# ModSynth_PCB.net
KiCad netlist of a schematic drawn in EAGLE
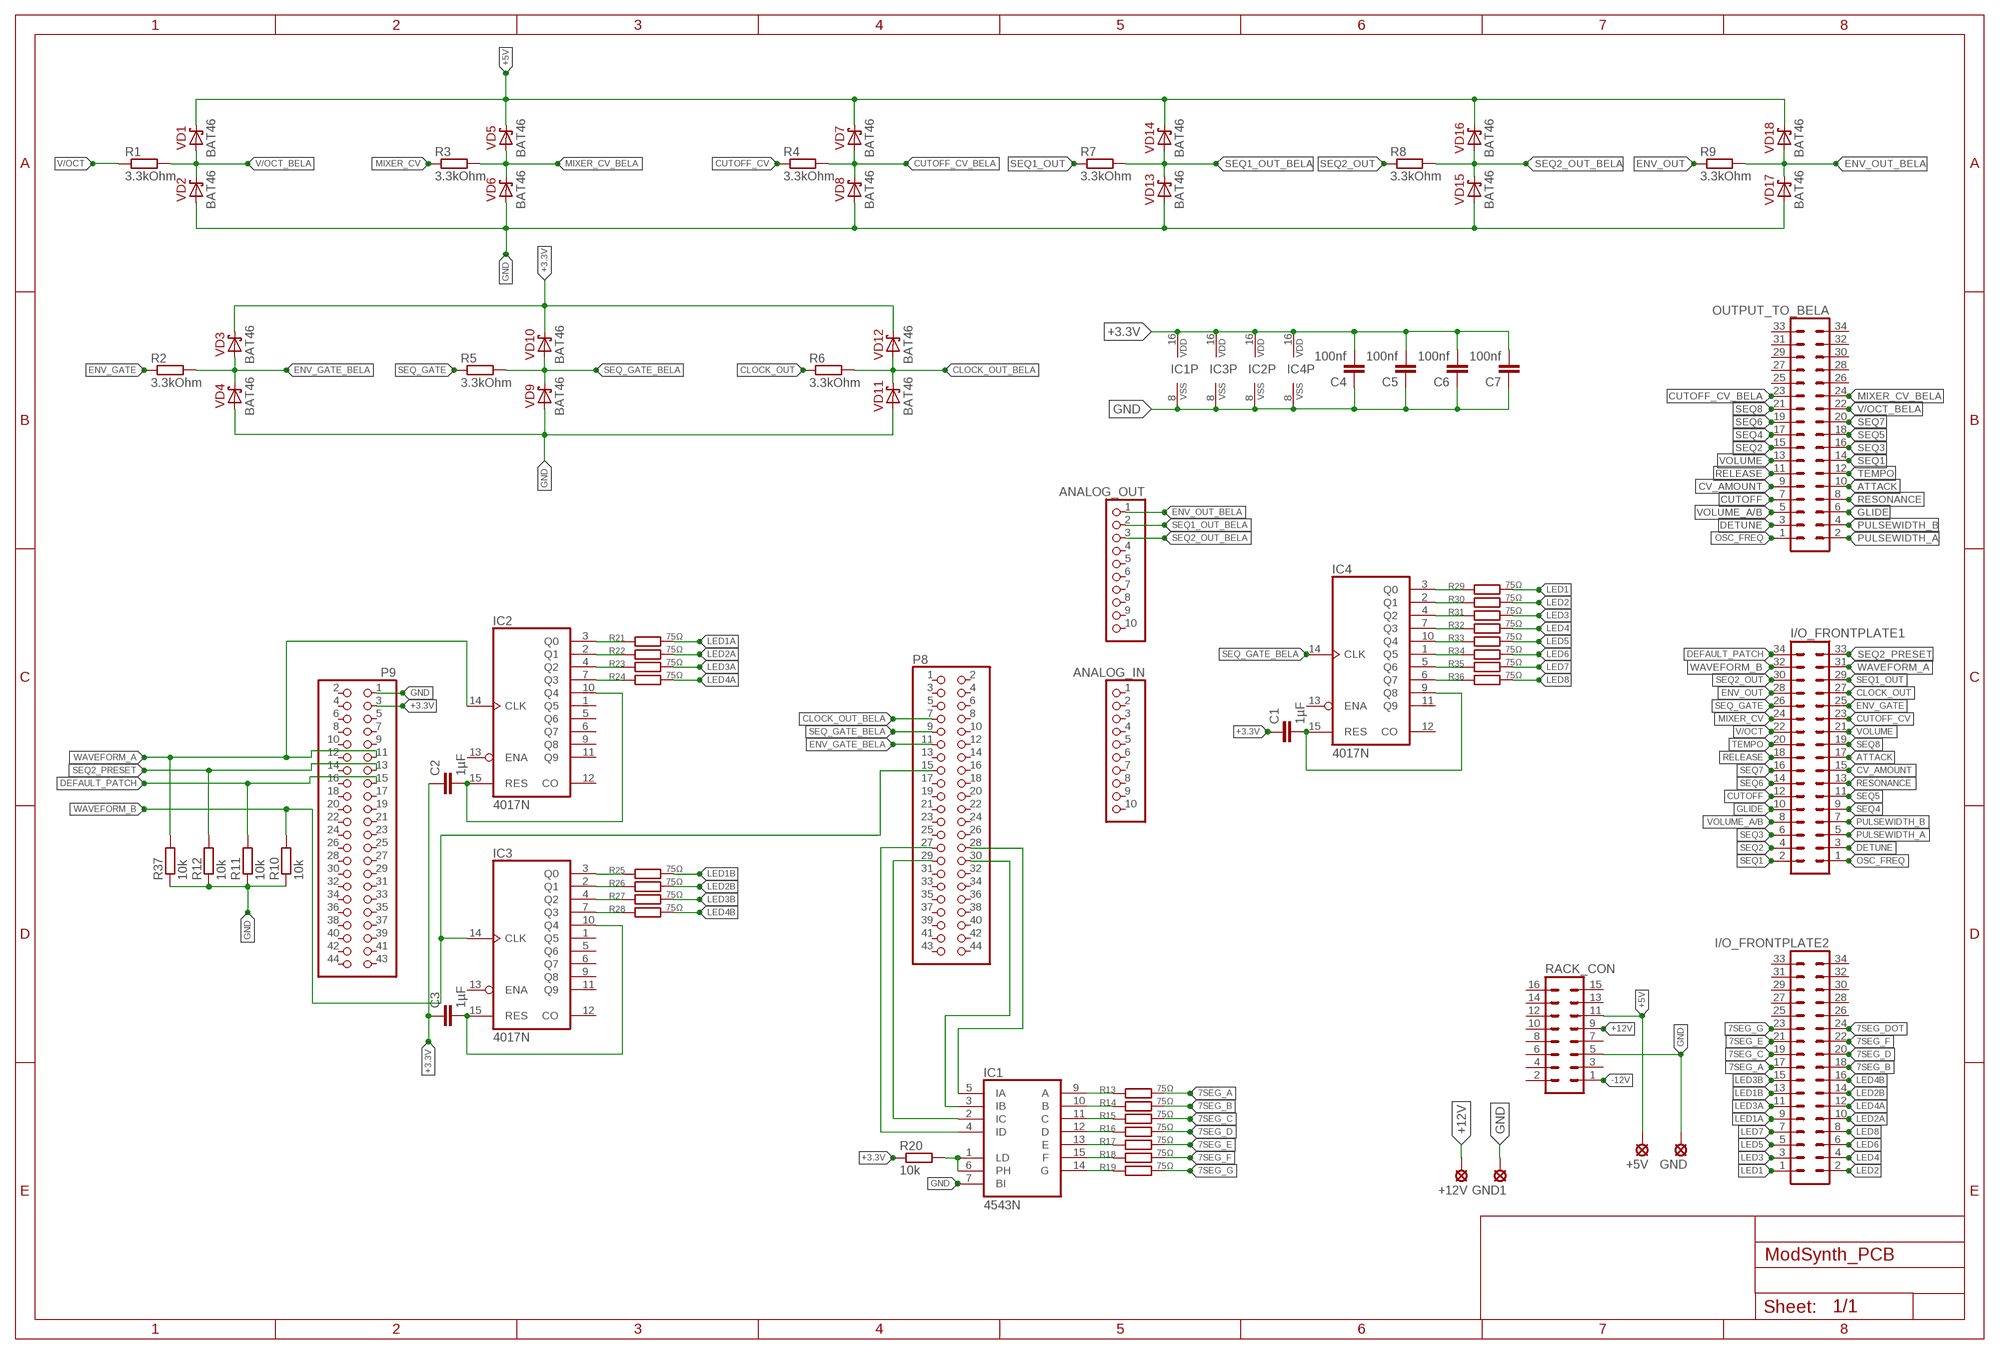
[diagram p0: schematic, sheet 1]

(export (version "E")
  (design (tool "Eeschema 10.0.6"))
  (components
    (comp (ref "+5V")
      (value "LSP10")
      (footprint "eagle-import:LSP10")
      (libsource (lib "eagle-import") (part "LSP10"))
    )
    (comp (ref "+12V")
      (value "LSP10")
      (footprint "eagle-import:LSP10")
      (libsource (lib "eagle-import") (part "LSP10"))
    )
    (comp (ref "ANALOG_IN")
      (value "PINHD-1X10")
      (footprint "eagle-import:1X10")
      (libsource (lib "eagle-import") (part "PINHD-1X10"))
    )
    (comp (ref "ANALOG_OUT")
      (value "PINHD-1X10")
      (footprint "eagle-import:1X10")
      (libsource (lib "eagle-import") (part "PINHD-1X10"))
    )
    (comp (ref "C1")
      (value "1µF")
      (footprint "eagle-import:C025-025X050")
      (libsource (lib "eagle-import") (part "C-EU025-025X050"))
    )
    (comp (ref "C2")
      (value "1µF")
      (footprint "eagle-import:C025-025X050")
      (libsource (lib "eagle-import") (part "C-EU025-025X050"))
    )
    (comp (ref "C3")
      (value "1µF")
      (footprint "eagle-import:C025-025X050")
      (libsource (lib "eagle-import") (part "C-EU025-025X050"))
    )
    (comp (ref "C4")
      (value "100nf")
      (footprint "eagle-import:C025-025X050")
      (libsource (lib "eagle-import") (part "C-EU025-025X050"))
    )
    (comp (ref "C5")
      (value "100nf")
      (footprint "eagle-import:C025-025X050")
      (libsource (lib "eagle-import") (part "C-EU025-025X050"))
    )
    (comp (ref "C6")
      (value "100nf")
      (footprint "eagle-import:C025-025X050")
      (libsource (lib "eagle-import") (part "C-EU025-025X050"))
    )
    (comp (ref "C7")
      (value "100nf")
      (footprint "eagle-import:C025-025X050")
      (libsource (lib "eagle-import") (part "C-EU025-025X050"))
    )
    (comp (ref "GND")
      (value "LSP10")
      (footprint "eagle-import:LSP10")
      (libsource (lib "eagle-import") (part "LSP10"))
    )
    (comp (ref "GND1")
      (value "LSP10")
      (footprint "eagle-import:LSP10")
      (libsource (lib "eagle-import") (part "LSP10"))
    )
    (comp (ref "I/O_FRONTPLATE1")
      (value "ML34")
      (footprint "eagle-import:ML34")
      (libsource (lib "eagle-import") (part "ML34"))
    )
    (comp (ref "I/O_FRONTPLATE2")
      (value "ML34")
      (footprint "eagle-import:ML34")
      (libsource (lib "eagle-import") (part "ML34"))
    )
    (comp (ref "IC1")
      (value "4543N")
      (footprint "eagle-import:DIL16")
      (libsource (lib "eagle-import") (part "4543N"))
    )
    (comp (ref "IC2")
      (value "4017N")
      (footprint "eagle-import:DIL16")
      (libsource (lib "eagle-import") (part "4017N"))
    )
    (comp (ref "IC3")
      (value "4017N")
      (footprint "eagle-import:DIL16")
      (libsource (lib "eagle-import") (part "4017N"))
    )
    (comp (ref "IC4")
      (value "4017N")
      (footprint "eagle-import:DIL16")
      (libsource (lib "eagle-import") (part "4017N"))
    )
    (comp (ref "OUTPUT_TO_BELA")
      (value "ML34")
      (footprint "eagle-import:ML34")
      (libsource (lib "eagle-import") (part "ML34"))
    )
    (comp (ref "P8")
      (value "PINHD-2X22")
      (footprint "eagle-import:2X22")
      (libsource (lib "eagle-import") (part "PINHD-2X22"))
    )
    (comp (ref "P9")
      (value "PINHD-2X22")
      (footprint "eagle-import:2X22")
      (libsource (lib "eagle-import") (part "PINHD-2X22"))
    )
    (comp (ref "R1")
      (value "3.3kOhm")
      (footprint "eagle-import:0204_7")
      (libsource (lib "eagle-import") (part "R-EU_0204/7"))
    )
    (comp (ref "R2")
      (value "3.3kOhm")
      (footprint "eagle-import:0204_7")
      (libsource (lib "eagle-import") (part "R-EU_0204/7"))
    )
    (comp (ref "R3")
      (value "3.3kOhm")
      (footprint "eagle-import:0204_7")
      (libsource (lib "eagle-import") (part "R-EU_0204/7"))
    )
    (comp (ref "R4")
      (value "3.3kOhm")
      (footprint "eagle-import:0204_7")
      (libsource (lib "eagle-import") (part "R-EU_0204/7"))
    )
    (comp (ref "R5")
      (value "3.3kOhm")
      (footprint "eagle-import:0204_7")
      (libsource (lib "eagle-import") (part "R-EU_0204/7"))
    )
    (comp (ref "R6")
      (value "3.3kOhm")
      (footprint "eagle-import:0204_7")
      (libsource (lib "eagle-import") (part "R-EU_0204/7"))
    )
    (comp (ref "R7")
      (value "3.3kOhm")
      (footprint "eagle-import:0204_7")
      (libsource (lib "eagle-import") (part "R-EU_0204/7"))
    )
    (comp (ref "R8")
      (value "3.3kOhm")
      (footprint "eagle-import:0204_7")
      (libsource (lib "eagle-import") (part "R-EU_0204/7"))
    )
    (comp (ref "R9")
      (value "3.3kOhm")
      (footprint "eagle-import:0204_7")
      (libsource (lib "eagle-import") (part "R-EU_0204/7"))
    )
    (comp (ref "R10")
      (value "10k")
      (footprint "eagle-import:0204_7")
      (libsource (lib "eagle-import") (part "R-EU_0204/7"))
    )
    (comp (ref "R11")
      (value "10k")
      (footprint "eagle-import:0204_7")
      (libsource (lib "eagle-import") (part "R-EU_0204/7"))
    )
    (comp (ref "R12")
      (value "10k")
      (footprint "eagle-import:0204_7")
      (libsource (lib "eagle-import") (part "R-EU_0204/7"))
    )
    (comp (ref "R13")
      (value "75Ω")
      (footprint "eagle-import:0204_7")
      (libsource (lib "eagle-import") (part "R-EU_0204/7"))
    )
    (comp (ref "R14")
      (value "75Ω")
      (footprint "eagle-import:0204_7")
      (libsource (lib "eagle-import") (part "R-EU_0204/7"))
    )
    (comp (ref "R15")
      (value "75Ω")
      (footprint "eagle-import:0204_7")
      (libsource (lib "eagle-import") (part "R-EU_0204/7"))
    )
    (comp (ref "R16")
      (value "75Ω")
      (footprint "eagle-import:0204_7")
      (libsource (lib "eagle-import") (part "R-EU_0204/7"))
    )
    (comp (ref "R17")
      (value "75Ω")
      (footprint "eagle-import:0204_7")
      (libsource (lib "eagle-import") (part "R-EU_0204/7"))
    )
    (comp (ref "R18")
      (value "75Ω")
      (footprint "eagle-import:0204_7")
      (libsource (lib "eagle-import") (part "R-EU_0204/7"))
    )
    (comp (ref "R19")
      (value "75Ω")
      (footprint "eagle-import:0204_7")
      (libsource (lib "eagle-import") (part "R-EU_0204/7"))
    )
    (comp (ref "R20")
      (value "10k")
      (footprint "eagle-import:0204_7")
      (libsource (lib "eagle-import") (part "R-EU_0204/7"))
    )
    (comp (ref "R21")
      (value "75Ω")
      (footprint "eagle-import:0204_7")
      (libsource (lib "eagle-import") (part "R-EU_0204/7"))
    )
    (comp (ref "R22")
      (value "75Ω")
      (footprint "eagle-import:0204_7")
      (libsource (lib "eagle-import") (part "R-EU_0204/7"))
    )
    (comp (ref "R23")
      (value "75Ω")
      (footprint "eagle-import:0204_7")
      (libsource (lib "eagle-import") (part "R-EU_0204/7"))
    )
    (comp (ref "R24")
      (value "75Ω")
      (footprint "eagle-import:0204_7")
      (libsource (lib "eagle-import") (part "R-EU_0204/7"))
    )
    (comp (ref "R25")
      (value "75Ω")
      (footprint "eagle-import:0204_7")
      (libsource (lib "eagle-import") (part "R-EU_0204/7"))
    )
    (comp (ref "R26")
      (value "75Ω")
      (footprint "eagle-import:0204_7")
      (libsource (lib "eagle-import") (part "R-EU_0204/7"))
    )
    (comp (ref "R27")
      (value "75Ω")
      (footprint "eagle-import:0204_7")
      (libsource (lib "eagle-import") (part "R-EU_0204/7"))
    )
    (comp (ref "R28")
      (value "75Ω")
      (footprint "eagle-import:0204_7")
      (libsource (lib "eagle-import") (part "R-EU_0204/7"))
    )
    (comp (ref "R29")
      (value "75Ω")
      (footprint "eagle-import:0204_7")
      (libsource (lib "eagle-import") (part "R-EU_0204/7"))
    )
    (comp (ref "R30")
      (value "75Ω")
      (footprint "eagle-import:0204_7")
      (libsource (lib "eagle-import") (part "R-EU_0204/7"))
    )
    (comp (ref "R31")
      (value "75Ω")
      (footprint "eagle-import:0204_7")
      (libsource (lib "eagle-import") (part "R-EU_0204/7"))
    )
    (comp (ref "R32")
      (value "75Ω")
      (footprint "eagle-import:0204_7")
      (libsource (lib "eagle-import") (part "R-EU_0204/7"))
    )
    (comp (ref "R33")
      (value "75Ω")
      (footprint "eagle-import:0204_7")
      (libsource (lib "eagle-import") (part "R-EU_0204/7"))
    )
    (comp (ref "R34")
      (value "75Ω")
      (footprint "eagle-import:0204_7")
      (libsource (lib "eagle-import") (part "R-EU_0204/7"))
    )
    (comp (ref "R35")
      (value "75Ω")
      (footprint "eagle-import:0204_7")
      (libsource (lib "eagle-import") (part "R-EU_0204/7"))
    )
    (comp (ref "R36")
      (value "75Ω")
      (footprint "eagle-import:0204_7")
      (libsource (lib "eagle-import") (part "R-EU_0204/7"))
    )
    (comp (ref "R37")
      (value "10k")
      (footprint "eagle-import:0204_7")
      (libsource (lib "eagle-import") (part "R-EU_0204/7"))
    )
    (comp (ref "RACK_CON")
      (value "ML16")
      (footprint "eagle-import:ML16")
      (libsource (lib "eagle-import") (part "ML16"))
    )
    (comp (ref "VD1")
      (value "BAT46")
      (footprint "eagle-import:DO35-7")
      (libsource (lib "eagle-import") (part "?BAT46"))
    )
    (comp (ref "VD2")
      (value "BAT46")
      (footprint "eagle-import:DO35-7")
      (libsource (lib "eagle-import") (part "?BAT46"))
    )
    (comp (ref "VD3")
      (value "BAT46")
      (footprint "eagle-import:DO35-7")
      (libsource (lib "eagle-import") (part "?BAT46"))
    )
    (comp (ref "VD4")
      (value "BAT46")
      (footprint "eagle-import:DO35-7")
      (libsource (lib "eagle-import") (part "?BAT46"))
    )
    (comp (ref "VD5")
      (value "BAT46")
      (footprint "eagle-import:DO35-7")
      (libsource (lib "eagle-import") (part "?BAT46"))
    )
    (comp (ref "VD6")
      (value "BAT46")
      (footprint "eagle-import:DO35-7")
      (libsource (lib "eagle-import") (part "?BAT46"))
    )
    (comp (ref "VD7")
      (value "BAT46")
      (footprint "eagle-import:DO35-7")
      (libsource (lib "eagle-import") (part "?BAT46"))
    )
    (comp (ref "VD8")
      (value "BAT46")
      (footprint "eagle-import:DO35-7")
      (libsource (lib "eagle-import") (part "?BAT46"))
    )
    (comp (ref "VD9")
      (value "BAT46")
      (footprint "eagle-import:DO35-7")
      (libsource (lib "eagle-import") (part "?BAT46"))
    )
    (comp (ref "VD10")
      (value "BAT46")
      (footprint "eagle-import:DO35-7")
      (libsource (lib "eagle-import") (part "?BAT46"))
    )
    (comp (ref "VD11")
      (value "BAT46")
      (footprint "eagle-import:DO35-7")
      (libsource (lib "eagle-import") (part "?BAT46"))
    )
    (comp (ref "VD12")
      (value "BAT46")
      (footprint "eagle-import:DO35-7")
      (libsource (lib "eagle-import") (part "?BAT46"))
    )
    (comp (ref "VD13")
      (value "BAT46")
      (footprint "eagle-import:DO35-7")
      (libsource (lib "eagle-import") (part "?BAT46"))
    )
    (comp (ref "VD14")
      (value "BAT46")
      (footprint "eagle-import:DO35-7")
      (libsource (lib "eagle-import") (part "?BAT46"))
    )
    (comp (ref "VD15")
      (value "BAT46")
      (footprint "eagle-import:DO35-7")
      (libsource (lib "eagle-import") (part "?BAT46"))
    )
    (comp (ref "VD16")
      (value "BAT46")
      (footprint "eagle-import:DO35-7")
      (libsource (lib "eagle-import") (part "?BAT46"))
    )
    (comp (ref "VD17")
      (value "BAT46")
      (footprint "eagle-import:DO35-7")
      (libsource (lib "eagle-import") (part "?BAT46"))
    )
    (comp (ref "VD18")
      (value "BAT46")
      (footprint "eagle-import:DO35-7")
      (libsource (lib "eagle-import") (part "?BAT46"))
    )
  )
  (nets
    (net (code "1") (name "+3.3V") (class "Default")
      (node (ref "C1") (pin "1") (pinfunction "1_1") (pintype "passive"))
      (node (ref "C2") (pin "1") (pinfunction "1_1") (pintype "passive"))
      (node (ref "C3") (pin "1") (pinfunction "1_1") (pintype "passive"))
      (node (ref "C4") (pin "2") (pinfunction "2_2") (pintype "passive"))
      (node (ref "C5") (pin "2") (pinfunction "2_2") (pintype "passive"))
      (node (ref "C6") (pin "2") (pinfunction "2_2") (pintype "passive"))
      (node (ref "C7") (pin "2") (pinfunction "2_2") (pintype "passive"))
      (node (ref "IC1") (pin "16") (pinfunction "VDD_16") (pintype "power_in"))
      (node (ref "IC2") (pin "16") (pinfunction "VDD_16") (pintype "power_in"))
      (node (ref "IC3") (pin "16") (pinfunction "VDD_16") (pintype "power_in"))
      (node (ref "IC4") (pin "16") (pinfunction "VDD_16") (pintype "power_in"))
      (node (ref "P9") (pin "3") (pinfunction "3_3") (pintype "passive"))
      (node (ref "R20") (pin "1") (pinfunction "1_1") (pintype "passive"))
      (node (ref "VD10") (pin "C") (pinfunction "C_C") (pintype "passive"))
      (node (ref "VD12") (pin "C") (pinfunction "C_C") (pintype "passive"))
      (node (ref "VD3") (pin "C") (pinfunction "C_C") (pintype "passive"))
    )
    (net (code "2") (name "+5V") (class "Default")
      (node (ref "+5V") (pin "MP") (pinfunction "MP_MP") (pintype "passive"))
      (node (ref "RACK_CON") (pin "11") (pinfunction "11_11") (pintype "passive"))
      (node (ref "VD1") (pin "C") (pinfunction "C_C") (pintype "passive"))
      (node (ref "VD14") (pin "C") (pinfunction "C_C") (pintype "passive"))
      (node (ref "VD16") (pin "C") (pinfunction "C_C") (pintype "passive"))
      (node (ref "VD18") (pin "C") (pinfunction "C_C") (pintype "passive"))
      (node (ref "VD5") (pin "C") (pinfunction "C_C") (pintype "passive"))
      (node (ref "VD7") (pin "C") (pinfunction "C_C") (pintype "passive"))
    )
    (net (code "3") (name "+12V") (class "Default")
      (node (ref "+12V") (pin "MP") (pinfunction "MP_MP") (pintype "passive"))
      (node (ref "RACK_CON") (pin "9") (pinfunction "9_9") (pintype "passive"))
    )
    (net (code "4") (name "-12V") (class "Default")
      (node (ref "RACK_CON") (pin "1") (pinfunction "1_1") (pintype "passive"))
    )
    (net (code "5") (name "7SEG_A") (class "Default")
      (node (ref "I/O_FRONTPLATE2") (pin "17") (pinfunction "17_17") (pintype "passive"))
      (node (ref "R13") (pin "2") (pinfunction "2_2") (pintype "passive"))
    )
    (net (code "6") (name "7SEG_B") (class "Default")
      (node (ref "I/O_FRONTPLATE2") (pin "18") (pinfunction "18_18") (pintype "passive"))
      (node (ref "R14") (pin "2") (pinfunction "2_2") (pintype "passive"))
    )
    (net (code "7") (name "7SEG_C") (class "Default")
      (node (ref "I/O_FRONTPLATE2") (pin "19") (pinfunction "19_19") (pintype "passive"))
      (node (ref "R15") (pin "2") (pinfunction "2_2") (pintype "passive"))
    )
    (net (code "8") (name "7SEG_D") (class "Default")
      (node (ref "I/O_FRONTPLATE2") (pin "20") (pinfunction "20_20") (pintype "passive"))
      (node (ref "R16") (pin "2") (pinfunction "2_2") (pintype "passive"))
    )
    (net (code "9") (name "7SEG_DOT") (class "Default")
      (node (ref "I/O_FRONTPLATE2") (pin "24") (pinfunction "24_24") (pintype "passive"))
    )
    (net (code "10") (name "7SEG_E") (class "Default")
      (node (ref "I/O_FRONTPLATE2") (pin "21") (pinfunction "21_21") (pintype "passive"))
      (node (ref "R17") (pin "2") (pinfunction "2_2") (pintype "passive"))
    )
    (net (code "11") (name "7SEG_F") (class "Default")
      (node (ref "I/O_FRONTPLATE2") (pin "22") (pinfunction "22_22") (pintype "passive"))
      (node (ref "R18") (pin "2") (pinfunction "2_2") (pintype "passive"))
    )
    (net (code "12") (name "7SEG_G") (class "Default")
      (node (ref "I/O_FRONTPLATE2") (pin "23") (pinfunction "23_23") (pintype "passive"))
      (node (ref "R19") (pin "2") (pinfunction "2_2") (pintype "passive"))
    )
    (net (code "13") (name "ATTACK") (class "Default")
      (node (ref "I/O_FRONTPLATE1") (pin "17") (pinfunction "17_17") (pintype "passive"))
      (node (ref "OUTPUT_TO_BELA") (pin "10") (pinfunction "10_10") (pintype "passive"))
    )
    (net (code "14") (name "CLOCK_OUT") (class "Default")
      (node (ref "I/O_FRONTPLATE1") (pin "27") (pinfunction "27_27") (pintype "passive"))
      (node (ref "R6") (pin "1") (pinfunction "1_1") (pintype "passive"))
    )
    (net (code "15") (name "CLOCK_OUT_BELA") (class "Default")
      (node (ref "P8") (pin "7") (pinfunction "7_7") (pintype "passive"))
      (node (ref "R6") (pin "2") (pinfunction "2_2") (pintype "passive"))
      (node (ref "VD11") (pin "C") (pinfunction "C_C") (pintype "passive"))
      (node (ref "VD12") (pin "A") (pinfunction "A_A") (pintype "passive"))
    )
    (net (code "16") (name "CUTOFF") (class "Default")
      (node (ref "I/O_FRONTPLATE1") (pin "12") (pinfunction "12_12") (pintype "passive"))
      (node (ref "OUTPUT_TO_BELA") (pin "7") (pinfunction "7_7") (pintype "passive"))
    )
    (net (code "17") (name "CUTOFF_CV") (class "Default")
      (node (ref "I/O_FRONTPLATE1") (pin "23") (pinfunction "23_23") (pintype "passive"))
      (node (ref "R4") (pin "1") (pinfunction "1_1") (pintype "passive"))
    )
    (net (code "18") (name "CUTOFF_CV_BELA") (class "Default")
      (node (ref "OUTPUT_TO_BELA") (pin "23") (pinfunction "23_23") (pintype "passive"))
      (node (ref "R4") (pin "2") (pinfunction "2_2") (pintype "passive"))
      (node (ref "VD7") (pin "A") (pinfunction "A_A") (pintype "passive"))
      (node (ref "VD8") (pin "C") (pinfunction "C_C") (pintype "passive"))
    )
    (net (code "19") (name "CV_AMOUNT") (class "Default")
      (node (ref "I/O_FRONTPLATE1") (pin "15") (pinfunction "15_15") (pintype "passive"))
      (node (ref "OUTPUT_TO_BELA") (pin "9") (pinfunction "9_9") (pintype "passive"))
    )
    (net (code "20") (name "DEFAULT_PATCH") (class "Default")
      (node (ref "I/O_FRONTPLATE1") (pin "34") (pinfunction "34_34") (pintype "passive"))
      (node (ref "P9") (pin "15") (pinfunction "15_15") (pintype "passive"))
      (node (ref "R11") (pin "2") (pinfunction "2_2") (pintype "passive"))
    )
    (net (code "21") (name "DETUNE") (class "Default")
      (node (ref "I/O_FRONTPLATE1") (pin "3") (pinfunction "3_3") (pintype "passive"))
      (node (ref "OUTPUT_TO_BELA") (pin "3") (pinfunction "3_3") (pintype "passive"))
    )
    (net (code "22") (name "ENV_GATE") (class "Default")
      (node (ref "I/O_FRONTPLATE1") (pin "25") (pinfunction "25_25") (pintype "passive"))
      (node (ref "R2") (pin "1") (pinfunction "1_1") (pintype "passive"))
    )
    (net (code "23") (name "ENV_GATE_BELA") (class "Default")
      (node (ref "P8") (pin "11") (pinfunction "11_11") (pintype "passive"))
      (node (ref "R2") (pin "2") (pinfunction "2_2") (pintype "passive"))
      (node (ref "VD3") (pin "A") (pinfunction "A_A") (pintype "passive"))
      (node (ref "VD4") (pin "C") (pinfunction "C_C") (pintype "passive"))
    )
    (net (code "24") (name "ENV_OUT") (class "Default")
      (node (ref "I/O_FRONTPLATE1") (pin "28") (pinfunction "28_28") (pintype "passive"))
      (node (ref "R9") (pin "1") (pinfunction "1_1") (pintype "passive"))
    )
    (net (code "25") (name "ENV_OUT_BELA") (class "Default")
      (node (ref "ANALOG_OUT") (pin "1") (pinfunction "1_1") (pintype "passive"))
      (node (ref "R9") (pin "2") (pinfunction "2_2") (pintype "passive"))
      (node (ref "VD17") (pin "C") (pinfunction "C_C") (pintype "passive"))
      (node (ref "VD18") (pin "A") (pinfunction "A_A") (pintype "passive"))
    )
    (net (code "26") (name "GLIDE") (class "Default")
      (node (ref "I/O_FRONTPLATE1") (pin "10") (pinfunction "10_10") (pintype "passive"))
      (node (ref "OUTPUT_TO_BELA") (pin "6") (pinfunction "6_6") (pintype "passive"))
    )
    (net (code "27") (name "GND") (class "Default")
      (node (ref "C4") (pin "1") (pinfunction "1_1") (pintype "passive"))
      (node (ref "C5") (pin "1") (pinfunction "1_1") (pintype "passive"))
      (node (ref "C6") (pin "1") (pinfunction "1_1") (pintype "passive"))
      (node (ref "C7") (pin "1") (pinfunction "1_1") (pintype "passive"))
      (node (ref "GND") (pin "MP") (pinfunction "MP_MP") (pintype "passive"))
      (node (ref "GND1") (pin "MP") (pinfunction "MP_MP") (pintype "passive"))
      (node (ref "IC1") (pin "7") (pinfunction "BI_7") (pintype "input"))
      (node (ref "IC1") (pin "8") (pinfunction "VSS_8") (pintype "power_in"))
      (node (ref "IC2") (pin "8") (pinfunction "VSS_8") (pintype "power_in"))
      (node (ref "IC3") (pin "8") (pinfunction "VSS_8") (pintype "power_in"))
      (node (ref "IC4") (pin "8") (pinfunction "VSS_8") (pintype "power_in"))
      (node (ref "P9") (pin "1") (pinfunction "1_1") (pintype "passive"))
      (node (ref "R10") (pin "1") (pinfunction "1_1") (pintype "passive"))
      (node (ref "R11") (pin "1") (pinfunction "1_1") (pintype "passive"))
      (node (ref "R12") (pin "1") (pinfunction "1_1") (pintype "passive"))
      (node (ref "R37") (pin "1") (pinfunction "1_1") (pintype "passive"))
      (node (ref "RACK_CON") (pin "5") (pinfunction "5_5") (pintype "passive"))
      (node (ref "VD11") (pin "A") (pinfunction "A_A") (pintype "passive"))
      (node (ref "VD13") (pin "A") (pinfunction "A_A") (pintype "passive"))
      (node (ref "VD15") (pin "A") (pinfunction "A_A") (pintype "passive"))
      (node (ref "VD17") (pin "A") (pinfunction "A_A") (pintype "passive"))
      (node (ref "VD2") (pin "A") (pinfunction "A_A") (pintype "passive"))
      (node (ref "VD4") (pin "A") (pinfunction "A_A") (pintype "passive"))
      (node (ref "VD6") (pin "A") (pinfunction "A_A") (pintype "passive"))
      (node (ref "VD8") (pin "A") (pinfunction "A_A") (pintype "passive"))
      (node (ref "VD9") (pin "A") (pinfunction "A_A") (pintype "passive"))
    )
    (net (code "28") (name "LED1") (class "Default")
      (node (ref "I/O_FRONTPLATE2") (pin "1") (pinfunction "1_1") (pintype "passive"))
      (node (ref "R29") (pin "2") (pinfunction "2_2") (pintype "passive"))
    )
    (net (code "29") (name "LED1A") (class "Default")
      (node (ref "I/O_FRONTPLATE2") (pin "9") (pinfunction "9_9") (pintype "passive"))
      (node (ref "R21") (pin "2") (pinfunction "2_2") (pintype "passive"))
    )
    (net (code "30") (name "LED1B") (class "Default")
      (node (ref "I/O_FRONTPLATE2") (pin "13") (pinfunction "13_13") (pintype "passive"))
      (node (ref "R25") (pin "2") (pinfunction "2_2") (pintype "passive"))
    )
    (net (code "31") (name "LED2") (class "Default")
      (node (ref "I/O_FRONTPLATE2") (pin "2") (pinfunction "2_2") (pintype "passive"))
      (node (ref "R30") (pin "2") (pinfunction "2_2") (pintype "passive"))
    )
    (net (code "32") (name "LED2A") (class "Default")
      (node (ref "I/O_FRONTPLATE2") (pin "10") (pinfunction "10_10") (pintype "passive"))
      (node (ref "R22") (pin "2") (pinfunction "2_2") (pintype "passive"))
    )
    (net (code "33") (name "LED2B") (class "Default")
      (node (ref "I/O_FRONTPLATE2") (pin "14") (pinfunction "14_14") (pintype "passive"))
      (node (ref "R26") (pin "2") (pinfunction "2_2") (pintype "passive"))
    )
    (net (code "34") (name "LED3") (class "Default")
      (node (ref "I/O_FRONTPLATE2") (pin "3") (pinfunction "3_3") (pintype "passive"))
      (node (ref "R31") (pin "2") (pinfunction "2_2") (pintype "passive"))
    )
    (net (code "35") (name "LED3A") (class "Default")
      (node (ref "I/O_FRONTPLATE2") (pin "11") (pinfunction "11_11") (pintype "passive"))
      (node (ref "R23") (pin "2") (pinfunction "2_2") (pintype "passive"))
    )
    (net (code "36") (name "LED3B") (class "Default")
      (node (ref "I/O_FRONTPLATE2") (pin "15") (pinfunction "15_15") (pintype "passive"))
      (node (ref "R27") (pin "2") (pinfunction "2_2") (pintype "passive"))
    )
    (net (code "37") (name "LED4") (class "Default")
      (node (ref "I/O_FRONTPLATE2") (pin "4") (pinfunction "4_4") (pintype "passive"))
      (node (ref "R32") (pin "2") (pinfunction "2_2") (pintype "passive"))
    )
    (net (code "38") (name "LED4A") (class "Default")
      (node (ref "I/O_FRONTPLATE2") (pin "12") (pinfunction "12_12") (pintype "passive"))
      (node (ref "R24") (pin "2") (pinfunction "2_2") (pintype "passive"))
    )
    (net (code "39") (name "LED4B") (class "Default")
      (node (ref "I/O_FRONTPLATE2") (pin "16") (pinfunction "16_16") (pintype "passive"))
      (node (ref "R28") (pin "2") (pinfunction "2_2") (pintype "passive"))
    )
    (net (code "40") (name "LED5") (class "Default")
      (node (ref "I/O_FRONTPLATE2") (pin "5") (pinfunction "5_5") (pintype "passive"))
      (node (ref "R33") (pin "2") (pinfunction "2_2") (pintype "passive"))
    )
    (net (code "41") (name "LED6") (class "Default")
      (node (ref "I/O_FRONTPLATE2") (pin "6") (pinfunction "6_6") (pintype "passive"))
      (node (ref "R34") (pin "2") (pinfunction "2_2") (pintype "passive"))
    )
    (net (code "42") (name "LED7") (class "Default")
      (node (ref "I/O_FRONTPLATE2") (pin "7") (pinfunction "7_7") (pintype "passive"))
      (node (ref "R35") (pin "2") (pinfunction "2_2") (pintype "passive"))
    )
    (net (code "43") (name "LED8") (class "Default")
      (node (ref "I/O_FRONTPLATE2") (pin "8") (pinfunction "8_8") (pintype "passive"))
      (node (ref "R36") (pin "2") (pinfunction "2_2") (pintype "passive"))
    )
    (net (code "44") (name "MIXER_CV") (class "Default")
      (node (ref "I/O_FRONTPLATE1") (pin "24") (pinfunction "24_24") (pintype "passive"))
      (node (ref "R3") (pin "1") (pinfunction "1_1") (pintype "passive"))
    )
    (net (code "45") (name "MIXER_CV_BELA") (class "Default")
      (node (ref "OUTPUT_TO_BELA") (pin "24") (pinfunction "24_24") (pintype "passive"))
      (node (ref "R3") (pin "2") (pinfunction "2_2") (pintype "passive"))
      (node (ref "VD5") (pin "A") (pinfunction "A_A") (pintype "passive"))
      (node (ref "VD6") (pin "C") (pinfunction "C_C") (pintype "passive"))
    )
    (net (code "46") (name "Net-(IC1A-A)") (class "Default")
      (node (ref "IC1") (pin "9") (pinfunction "A_9") (pintype "output"))
      (node (ref "R13") (pin "1") (pinfunction "1_1") (pintype "passive"))
    )
    (net (code "47") (name "Net-(IC1A-B)") (class "Default")
      (node (ref "IC1") (pin "10") (pinfunction "B_10") (pintype "output"))
      (node (ref "R14") (pin "1") (pinfunction "1_1") (pintype "passive"))
    )
    (net (code "48") (name "Net-(IC1A-C)") (class "Default")
      (node (ref "IC1") (pin "11") (pinfunction "C_11") (pintype "output"))
      (node (ref "R15") (pin "1") (pinfunction "1_1") (pintype "passive"))
    )
    (net (code "49") (name "Net-(IC1A-D)") (class "Default")
      (node (ref "IC1") (pin "12") (pinfunction "D_12") (pintype "output"))
      (node (ref "R16") (pin "1") (pinfunction "1_1") (pintype "passive"))
    )
    (net (code "50") (name "Net-(IC1A-E)") (class "Default")
      (node (ref "IC1") (pin "13") (pinfunction "E_13") (pintype "output"))
      (node (ref "R17") (pin "1") (pinfunction "1_1") (pintype "passive"))
    )
    (net (code "51") (name "Net-(IC1A-F)") (class "Default")
      (node (ref "IC1") (pin "15") (pinfunction "F_15") (pintype "output"))
      (node (ref "R18") (pin "1") (pinfunction "1_1") (pintype "passive"))
    )
    (net (code "52") (name "Net-(IC1A-G)") (class "Default")
      (node (ref "IC1") (pin "14") (pinfunction "G_14") (pintype "output"))
      (node (ref "R19") (pin "1") (pinfunction "1_1") (pintype "passive"))
    )
    (net (code "53") (name "Net-(IC1A-IA)") (class "Default")
      (node (ref "IC1") (pin "5") (pinfunction "IA_5") (pintype "input"))
      (node (ref "P8") (pin "28") (pinfunction "28_28") (pintype "passive"))
    )
    (net (code "54") (name "Net-(IC1A-IB)") (class "Default")
      (node (ref "IC1") (pin "3") (pinfunction "IB_3") (pintype "input"))
      (node (ref "P8") (pin "30") (pinfunction "30_30") (pintype "passive"))
    )
    (net (code "55") (name "Net-(IC1A-IC)") (class "Default")
      (node (ref "IC1") (pin "2") (pinfunction "IC_2") (pintype "input"))
      (node (ref "P8") (pin "29") (pinfunction "29_29") (pintype "passive"))
    )
    (net (code "56") (name "Net-(IC1A-ID)") (class "Default")
      (node (ref "IC1") (pin "4") (pinfunction "ID_4") (pintype "input"))
      (node (ref "P8") (pin "27") (pinfunction "27_27") (pintype "passive"))
    )
    (net (code "57") (name "Net-(IC1A-LD)") (class "Default")
      (node (ref "IC1") (pin "1") (pinfunction "LD_1") (pintype "input"))
      (node (ref "IC1") (pin "6") (pinfunction "PH_6") (pintype "input"))
      (node (ref "R20") (pin "2") (pinfunction "2_2") (pintype "passive"))
    )
    (net (code "58") (name "Net-(IC2A-Q0)") (class "Default")
      (node (ref "IC2") (pin "3") (pinfunction "Q0_3") (pintype "output"))
      (node (ref "R21") (pin "1") (pinfunction "1_1") (pintype "passive"))
    )
    (net (code "59") (name "Net-(IC2A-Q1)") (class "Default")
      (node (ref "IC2") (pin "2") (pinfunction "Q1_2") (pintype "output"))
      (node (ref "R22") (pin "1") (pinfunction "1_1") (pintype "passive"))
    )
    (net (code "60") (name "Net-(IC2A-Q2)") (class "Default")
      (node (ref "IC2") (pin "4") (pinfunction "Q2_4") (pintype "output"))
      (node (ref "R23") (pin "1") (pinfunction "1_1") (pintype "passive"))
    )
    (net (code "61") (name "Net-(IC2A-Q3)") (class "Default")
      (node (ref "IC2") (pin "7") (pinfunction "Q3_7") (pintype "output"))
      (node (ref "R24") (pin "1") (pinfunction "1_1") (pintype "passive"))
    )
    (net (code "62") (name "Net-(IC2A-Q4)") (class "Default")
      (node (ref "C2") (pin "2") (pinfunction "2_2") (pintype "passive"))
      (node (ref "IC2") (pin "10") (pinfunction "Q4_10") (pintype "output"))
      (node (ref "IC2") (pin "15") (pinfunction "RES_15") (pintype "input"))
    )
    (net (code "63") (name "Net-(IC3A-Q0)") (class "Default")
      (node (ref "IC3") (pin "3") (pinfunction "Q0_3") (pintype "output"))
      (node (ref "R25") (pin "1") (pinfunction "1_1") (pintype "passive"))
    )
    (net (code "64") (name "Net-(IC3A-Q1)") (class "Default")
      (node (ref "IC3") (pin "2") (pinfunction "Q1_2") (pintype "output"))
      (node (ref "R26") (pin "1") (pinfunction "1_1") (pintype "passive"))
    )
    (net (code "65") (name "Net-(IC3A-Q2)") (class "Default")
      (node (ref "IC3") (pin "4") (pinfunction "Q2_4") (pintype "output"))
      (node (ref "R27") (pin "1") (pinfunction "1_1") (pintype "passive"))
    )
    (net (code "66") (name "Net-(IC3A-Q3)") (class "Default")
      (node (ref "IC3") (pin "7") (pinfunction "Q3_7") (pintype "output"))
      (node (ref "R28") (pin "1") (pinfunction "1_1") (pintype "passive"))
    )
    (net (code "67") (name "Net-(IC3A-Q4)") (class "Default")
      (node (ref "C3") (pin "2") (pinfunction "2_2") (pintype "passive"))
      (node (ref "IC3") (pin "10") (pinfunction "Q4_10") (pintype "output"))
      (node (ref "IC3") (pin "15") (pinfunction "RES_15") (pintype "input"))
    )
    (net (code "68") (name "Net-(IC4A-Q0)") (class "Default")
      (node (ref "IC4") (pin "3") (pinfunction "Q0_3") (pintype "output"))
      (node (ref "R29") (pin "1") (pinfunction "1_1") (pintype "passive"))
    )
    (net (code "69") (name "Net-(IC4A-Q1)") (class "Default")
      (node (ref "IC4") (pin "2") (pinfunction "Q1_2") (pintype "output"))
      (node (ref "R30") (pin "1") (pinfunction "1_1") (pintype "passive"))
    )
    (net (code "70") (name "Net-(IC4A-Q2)") (class "Default")
      (node (ref "IC4") (pin "4") (pinfunction "Q2_4") (pintype "output"))
      (node (ref "R31") (pin "1") (pinfunction "1_1") (pintype "passive"))
    )
    (net (code "71") (name "Net-(IC4A-Q3)") (class "Default")
      (node (ref "IC4") (pin "7") (pinfunction "Q3_7") (pintype "output"))
      (node (ref "R32") (pin "1") (pinfunction "1_1") (pintype "passive"))
    )
    (net (code "72") (name "Net-(IC4A-Q4)") (class "Default")
      (node (ref "IC4") (pin "10") (pinfunction "Q4_10") (pintype "output"))
      (node (ref "R33") (pin "1") (pinfunction "1_1") (pintype "passive"))
    )
    (net (code "73") (name "Net-(IC4A-Q5)") (class "Default")
      (node (ref "IC4") (pin "1") (pinfunction "Q5_1") (pintype "output"))
      (node (ref "R34") (pin "1") (pinfunction "1_1") (pintype "passive"))
    )
    (net (code "74") (name "Net-(IC4A-Q6)") (class "Default")
      (node (ref "IC4") (pin "5") (pinfunction "Q6_5") (pintype "output"))
      (node (ref "R35") (pin "1") (pinfunction "1_1") (pintype "passive"))
    )
    (net (code "75") (name "Net-(IC4A-Q7)") (class "Default")
      (node (ref "IC4") (pin "6") (pinfunction "Q7_6") (pintype "output"))
      (node (ref "R36") (pin "1") (pinfunction "1_1") (pintype "passive"))
    )
    (net (code "76") (name "Net-(IC4A-Q8)") (class "Default")
      (node (ref "C1") (pin "2") (pinfunction "2_2") (pintype "passive"))
      (node (ref "IC4") (pin "15") (pinfunction "RES_15") (pintype "input"))
      (node (ref "IC4") (pin "9") (pinfunction "Q8_9") (pintype "output"))
    )
    (net (code "77") (name "OSC_FREQ") (class "Default")
      (node (ref "I/O_FRONTPLATE1") (pin "1") (pinfunction "1_1") (pintype "passive"))
      (node (ref "OUTPUT_TO_BELA") (pin "1") (pinfunction "1_1") (pintype "passive"))
    )
    (net (code "78") (name "PULSEWIDTH_A") (class "Default")
      (node (ref "I/O_FRONTPLATE1") (pin "5") (pinfunction "5_5") (pintype "passive"))
      (node (ref "OUTPUT_TO_BELA") (pin "2") (pinfunction "2_2") (pintype "passive"))
    )
    (net (code "79") (name "PULSEWIDTH_B") (class "Default")
      (node (ref "I/O_FRONTPLATE1") (pin "7") (pinfunction "7_7") (pintype "passive"))
      (node (ref "OUTPUT_TO_BELA") (pin "4") (pinfunction "4_4") (pintype "passive"))
    )
    (net (code "80") (name "RELEASE") (class "Default")
      (node (ref "I/O_FRONTPLATE1") (pin "18") (pinfunction "18_18") (pintype "passive"))
      (node (ref "OUTPUT_TO_BELA") (pin "11") (pinfunction "11_11") (pintype "passive"))
    )
    (net (code "81") (name "RESONANCE") (class "Default")
      (node (ref "I/O_FRONTPLATE1") (pin "13") (pinfunction "13_13") (pintype "passive"))
      (node (ref "OUTPUT_TO_BELA") (pin "8") (pinfunction "8_8") (pintype "passive"))
    )
    (net (code "82") (name "SEQ1") (class "Default")
      (node (ref "I/O_FRONTPLATE1") (pin "2") (pinfunction "2_2") (pintype "passive"))
      (node (ref "OUTPUT_TO_BELA") (pin "14") (pinfunction "14_14") (pintype "passive"))
    )
    (net (code "83") (name "SEQ1_OUT") (class "Default")
      (node (ref "I/O_FRONTPLATE1") (pin "29") (pinfunction "29_29") (pintype "passive"))
      (node (ref "R7") (pin "1") (pinfunction "1_1") (pintype "passive"))
    )
    (net (code "84") (name "SEQ1_OUT_BELA") (class "Default")
      (node (ref "ANALOG_OUT") (pin "2") (pinfunction "2_2") (pintype "passive"))
      (node (ref "R7") (pin "2") (pinfunction "2_2") (pintype "passive"))
      (node (ref "VD13") (pin "C") (pinfunction "C_C") (pintype "passive"))
      (node (ref "VD14") (pin "A") (pinfunction "A_A") (pintype "passive"))
    )
    (net (code "85") (name "SEQ2") (class "Default")
      (node (ref "I/O_FRONTPLATE1") (pin "4") (pinfunction "4_4") (pintype "passive"))
      (node (ref "OUTPUT_TO_BELA") (pin "15") (pinfunction "15_15") (pintype "passive"))
    )
    (net (code "86") (name "SEQ2_OUT") (class "Default")
      (node (ref "I/O_FRONTPLATE1") (pin "30") (pinfunction "30_30") (pintype "passive"))
      (node (ref "R8") (pin "1") (pinfunction "1_1") (pintype "passive"))
    )
    (net (code "87") (name "SEQ2_OUT_BELA") (class "Default")
      (node (ref "ANALOG_OUT") (pin "3") (pinfunction "3_3") (pintype "passive"))
      (node (ref "R8") (pin "2") (pinfunction "2_2") (pintype "passive"))
      (node (ref "VD15") (pin "C") (pinfunction "C_C") (pintype "passive"))
      (node (ref "VD16") (pin "A") (pinfunction "A_A") (pintype "passive"))
    )
    (net (code "88") (name "SEQ2_PRESET") (class "Default")
      (node (ref "I/O_FRONTPLATE1") (pin "33") (pinfunction "33_33") (pintype "passive"))
      (node (ref "P9") (pin "13") (pinfunction "13_13") (pintype "passive"))
      (node (ref "R12") (pin "2") (pinfunction "2_2") (pintype "passive"))
    )
    (net (code "89") (name "SEQ3") (class "Default")
      (node (ref "I/O_FRONTPLATE1") (pin "6") (pinfunction "6_6") (pintype "passive"))
      (node (ref "OUTPUT_TO_BELA") (pin "16") (pinfunction "16_16") (pintype "passive"))
    )
    (net (code "90") (name "SEQ4") (class "Default")
      (node (ref "I/O_FRONTPLATE1") (pin "9") (pinfunction "9_9") (pintype "passive"))
      (node (ref "OUTPUT_TO_BELA") (pin "17") (pinfunction "17_17") (pintype "passive"))
    )
    (net (code "91") (name "SEQ5") (class "Default")
      (node (ref "I/O_FRONTPLATE1") (pin "11") (pinfunction "11_11") (pintype "passive"))
      (node (ref "OUTPUT_TO_BELA") (pin "18") (pinfunction "18_18") (pintype "passive"))
    )
    (net (code "92") (name "SEQ6") (class "Default")
      (node (ref "I/O_FRONTPLATE1") (pin "14") (pinfunction "14_14") (pintype "passive"))
      (node (ref "OUTPUT_TO_BELA") (pin "19") (pinfunction "19_19") (pintype "passive"))
    )
    (net (code "93") (name "SEQ7") (class "Default")
      (node (ref "I/O_FRONTPLATE1") (pin "16") (pinfunction "16_16") (pintype "passive"))
      (node (ref "OUTPUT_TO_BELA") (pin "20") (pinfunction "20_20") (pintype "passive"))
    )
    (net (code "94") (name "SEQ8") (class "Default")
      (node (ref "I/O_FRONTPLATE1") (pin "19") (pinfunction "19_19") (pintype "passive"))
      (node (ref "OUTPUT_TO_BELA") (pin "21") (pinfunction "21_21") (pintype "passive"))
    )
    (net (code "95") (name "SEQ_GATE") (class "Default")
      (node (ref "I/O_FRONTPLATE1") (pin "26") (pinfunction "26_26") (pintype "passive"))
      (node (ref "R5") (pin "1") (pinfunction "1_1") (pintype "passive"))
    )
    (net (code "96") (name "SEQ_GATE_BELA") (class "Default")
      (node (ref "IC4") (pin "14") (pinfunction "CLK_14") (pintype "input"))
      (node (ref "P8") (pin "9") (pinfunction "9_9") (pintype "passive"))
      (node (ref "R5") (pin "2") (pinfunction "2_2") (pintype "passive"))
      (node (ref "VD10") (pin "A") (pinfunction "A_A") (pintype "passive"))
      (node (ref "VD9") (pin "C") (pinfunction "C_C") (pintype "passive"))
    )
    (net (code "97") (name "TEMPO") (class "Default")
      (node (ref "I/O_FRONTPLATE1") (pin "20") (pinfunction "20_20") (pintype "passive"))
      (node (ref "OUTPUT_TO_BELA") (pin "12") (pinfunction "12_12") (pintype "passive"))
    )
    (net (code "98") (name "VOLUME") (class "Default")
      (node (ref "I/O_FRONTPLATE1") (pin "21") (pinfunction "21_21") (pintype "passive"))
      (node (ref "OUTPUT_TO_BELA") (pin "13") (pinfunction "13_13") (pintype "passive"))
    )
    (net (code "99") (name "VOLUME_A{slash}B") (class "Default")
      (node (ref "I/O_FRONTPLATE1") (pin "8") (pinfunction "8_8") (pintype "passive"))
      (node (ref "OUTPUT_TO_BELA") (pin "5") (pinfunction "5_5") (pintype "passive"))
    )
    (net (code "100") (name "V{slash}OCT") (class "Default")
      (node (ref "I/O_FRONTPLATE1") (pin "22") (pinfunction "22_22") (pintype "passive"))
      (node (ref "R1") (pin "1") (pinfunction "1_1") (pintype "passive"))
    )
    (net (code "101") (name "V{slash}OCT_BELA") (class "Default")
      (node (ref "OUTPUT_TO_BELA") (pin "22") (pinfunction "22_22") (pintype "passive"))
      (node (ref "R1") (pin "2") (pinfunction "2_2") (pintype "passive"))
      (node (ref "VD1") (pin "A") (pinfunction "A_A") (pintype "passive"))
      (node (ref "VD2") (pin "C") (pinfunction "C_C") (pintype "passive"))
    )
    (net (code "102") (name "WAVEFORM_A") (class "Default")
      (node (ref "I/O_FRONTPLATE1") (pin "31") (pinfunction "31_31") (pintype "passive"))
      (node (ref "IC2") (pin "14") (pinfunction "CLK_14") (pintype "input"))
      (node (ref "P9") (pin "11") (pinfunction "11_11") (pintype "passive"))
      (node (ref "R37") (pin "2") (pinfunction "2_2") (pintype "passive"))
    )
    (net (code "103") (name "WAVEFORM_B") (class "Default")
      (node (ref "I/O_FRONTPLATE1") (pin "32") (pinfunction "32_32") (pintype "passive"))
      (node (ref "IC3") (pin "14") (pinfunction "CLK_14") (pintype "input"))
      (node (ref "P8") (pin "15") (pinfunction "15_15") (pintype "passive"))
      (node (ref "R10") (pin "2") (pinfunction "2_2") (pintype "passive"))
    )
    (net (code "104") (name "unconnected-(ANALOG_IN-Pad1)") (class "Default")
      (node (ref "ANALOG_IN") (pin "1") (pinfunction "1_1") (pintype "passive"))
    )
    (net (code "105") (name "unconnected-(ANALOG_IN-Pad2)") (class "Default")
      (node (ref "ANALOG_IN") (pin "2") (pinfunction "2_2") (pintype "passive"))
    )
    (net (code "106") (name "unconnected-(ANALOG_IN-Pad3)") (class "Default")
      (node (ref "ANALOG_IN") (pin "3") (pinfunction "3_3") (pintype "passive"))
    )
    (net (code "107") (name "unconnected-(ANALOG_IN-Pad4)") (class "Default")
      (node (ref "ANALOG_IN") (pin "4") (pinfunction "4_4") (pintype "passive"))
    )
    (net (code "108") (name "unconnected-(ANALOG_IN-Pad5)") (class "Default")
      (node (ref "ANALOG_IN") (pin "5") (pinfunction "5_5") (pintype "passive"))
    )
    (net (code "109") (name "unconnected-(ANALOG_IN-Pad6)") (class "Default")
      (node (ref "ANALOG_IN") (pin "6") (pinfunction "6_6") (pintype "passive"))
    )
    (net (code "110") (name "unconnected-(ANALOG_IN-Pad7)") (class "Default")
      (node (ref "ANALOG_IN") (pin "7") (pinfunction "7_7") (pintype "passive"))
    )
    (net (code "111") (name "unconnected-(ANALOG_IN-Pad8)") (class "Default")
      (node (ref "ANALOG_IN") (pin "8") (pinfunction "8_8") (pintype "passive"))
    )
    (net (code "112") (name "unconnected-(ANALOG_IN-Pad9)") (class "Default")
      (node (ref "ANALOG_IN") (pin "9") (pinfunction "9_9") (pintype "passive"))
    )
    (net (code "113") (name "unconnected-(ANALOG_IN-Pad10)") (class "Default")
      (node (ref "ANALOG_IN") (pin "10") (pinfunction "10_10") (pintype "passive"))
    )
    (net (code "114") (name "unconnected-(ANALOG_OUT-Pad4)") (class "Default")
      (node (ref "ANALOG_OUT") (pin "4") (pinfunction "4_4") (pintype "passive"))
    )
    (net (code "115") (name "unconnected-(ANALOG_OUT-Pad5)") (class "Default")
      (node (ref "ANALOG_OUT") (pin "5") (pinfunction "5_5") (pintype "passive"))
    )
    (net (code "116") (name "unconnected-(ANALOG_OUT-Pad6)") (class "Default")
      (node (ref "ANALOG_OUT") (pin "6") (pinfunction "6_6") (pintype "passive"))
    )
    (net (code "117") (name "unconnected-(ANALOG_OUT-Pad7)") (class "Default")
      (node (ref "ANALOG_OUT") (pin "7") (pinfunction "7_7") (pintype "passive"))
    )
    (net (code "118") (name "unconnected-(ANALOG_OUT-Pad8)") (class "Default")
      (node (ref "ANALOG_OUT") (pin "8") (pinfunction "8_8") (pintype "passive"))
    )
    (net (code "119") (name "unconnected-(ANALOG_OUT-Pad9)") (class "Default")
      (node (ref "ANALOG_OUT") (pin "9") (pinfunction "9_9") (pintype "passive"))
    )
    (net (code "120") (name "unconnected-(ANALOG_OUT-Pad10)") (class "Default")
      (node (ref "ANALOG_OUT") (pin "10") (pinfunction "10_10") (pintype "passive"))
    )
    (net (code "121") (name "unconnected-(I/O_FRONTPLATE2-Pad25)") (class "Default")
      (node (ref "I/O_FRONTPLATE2") (pin "25") (pinfunction "25_25") (pintype "passive"))
    )
    (net (code "122") (name "unconnected-(I/O_FRONTPLATE2-Pad26)") (class "Default")
      (node (ref "I/O_FRONTPLATE2") (pin "26") (pinfunction "26_26") (pintype "passive"))
    )
    (net (code "123") (name "unconnected-(I/O_FRONTPLATE2-Pad27)") (class "Default")
      (node (ref "I/O_FRONTPLATE2") (pin "27") (pinfunction "27_27") (pintype "passive"))
    )
    (net (code "124") (name "unconnected-(I/O_FRONTPLATE2-Pad28)") (class "Default")
      (node (ref "I/O_FRONTPLATE2") (pin "28") (pinfunction "28_28") (pintype "passive"))
    )
    (net (code "125") (name "unconnected-(I/O_FRONTPLATE2-Pad29)") (class "Default")
      (node (ref "I/O_FRONTPLATE2") (pin "29") (pinfunction "29_29") (pintype "passive"))
    )
    (net (code "126") (name "unconnected-(I/O_FRONTPLATE2-Pad30)") (class "Default")
      (node (ref "I/O_FRONTPLATE2") (pin "30") (pinfunction "30_30") (pintype "passive"))
    )
    (net (code "127") (name "unconnected-(I/O_FRONTPLATE2-Pad31)") (class "Default")
      (node (ref "I/O_FRONTPLATE2") (pin "31") (pinfunction "31_31") (pintype "passive"))
    )
    (net (code "128") (name "unconnected-(I/O_FRONTPLATE2-Pad32)") (class "Default")
      (node (ref "I/O_FRONTPLATE2") (pin "32") (pinfunction "32_32") (pintype "passive"))
    )
    (net (code "129") (name "unconnected-(I/O_FRONTPLATE2-Pad33)") (class "Default")
      (node (ref "I/O_FRONTPLATE2") (pin "33") (pinfunction "33_33") (pintype "passive"))
    )
    (net (code "130") (name "unconnected-(I/O_FRONTPLATE2-Pad34)") (class "Default")
      (node (ref "I/O_FRONTPLATE2") (pin "34") (pinfunction "34_34") (pintype "passive"))
    )
    (net (code "131") (name "unconnected-(IC2A-CO-Pad12)") (class "Default")
      (node (ref "IC2") (pin "12") (pinfunction "CO_12") (pintype "output"))
    )
    (net (code "132") (name "unconnected-(IC2A-ENA-Pad13)") (class "Default")
      (node (ref "IC2") (pin "13") (pinfunction "ENA_13") (pintype "input"))
    )
    (net (code "133") (name "unconnected-(IC2A-Q5-Pad1)") (class "Default")
      (node (ref "IC2") (pin "1") (pinfunction "Q5_1") (pintype "output"))
    )
    (net (code "134") (name "unconnected-(IC2A-Q6-Pad5)") (class "Default")
      (node (ref "IC2") (pin "5") (pinfunction "Q6_5") (pintype "output"))
    )
    (net (code "135") (name "unconnected-(IC2A-Q7-Pad6)") (class "Default")
      (node (ref "IC2") (pin "6") (pinfunction "Q7_6") (pintype "output"))
    )
    (net (code "136") (name "unconnected-(IC2A-Q8-Pad9)") (class "Default")
      (node (ref "IC2") (pin "9") (pinfunction "Q8_9") (pintype "output"))
    )
    (net (code "137") (name "unconnected-(IC2A-Q9-Pad11)") (class "Default")
      (node (ref "IC2") (pin "11") (pinfunction "Q9_11") (pintype "output"))
    )
    (net (code "138") (name "unconnected-(IC3A-CO-Pad12)") (class "Default")
      (node (ref "IC3") (pin "12") (pinfunction "CO_12") (pintype "output"))
    )
    (net (code "139") (name "unconnected-(IC3A-ENA-Pad13)") (class "Default")
      (node (ref "IC3") (pin "13") (pinfunction "ENA_13") (pintype "input"))
    )
    (net (code "140") (name "unconnected-(IC3A-Q5-Pad1)") (class "Default")
      (node (ref "IC3") (pin "1") (pinfunction "Q5_1") (pintype "output"))
    )
    (net (code "141") (name "unconnected-(IC3A-Q6-Pad5)") (class "Default")
      (node (ref "IC3") (pin "5") (pinfunction "Q6_5") (pintype "output"))
    )
    (net (code "142") (name "unconnected-(IC3A-Q7-Pad6)") (class "Default")
      (node (ref "IC3") (pin "6") (pinfunction "Q7_6") (pintype "output"))
    )
    (net (code "143") (name "unconnected-(IC3A-Q8-Pad9)") (class "Default")
      (node (ref "IC3") (pin "9") (pinfunction "Q8_9") (pintype "output"))
    )
    (net (code "144") (name "unconnected-(IC3A-Q9-Pad11)") (class "Default")
      (node (ref "IC3") (pin "11") (pinfunction "Q9_11") (pintype "output"))
    )
    (net (code "145") (name "unconnected-(IC4A-CO-Pad12)") (class "Default")
      (node (ref "IC4") (pin "12") (pinfunction "CO_12") (pintype "output"))
    )
    (net (code "146") (name "unconnected-(IC4A-ENA-Pad13)") (class "Default")
      (node (ref "IC4") (pin "13") (pinfunction "ENA_13") (pintype "input"))
    )
    (net (code "147") (name "unconnected-(IC4A-Q9-Pad11)") (class "Default")
      (node (ref "IC4") (pin "11") (pinfunction "Q9_11") (pintype "output"))
    )
    (net (code "148") (name "unconnected-(OUTPUT_TO_BELA-Pad25)") (class "Default")
      (node (ref "OUTPUT_TO_BELA") (pin "25") (pinfunction "25_25") (pintype "passive"))
    )
    (net (code "149") (name "unconnected-(OUTPUT_TO_BELA-Pad26)") (class "Default")
      (node (ref "OUTPUT_TO_BELA") (pin "26") (pinfunction "26_26") (pintype "passive"))
    )
    (net (code "150") (name "unconnected-(OUTPUT_TO_BELA-Pad27)") (class "Default")
      (node (ref "OUTPUT_TO_BELA") (pin "27") (pinfunction "27_27") (pintype "passive"))
    )
    (net (code "151") (name "unconnected-(OUTPUT_TO_BELA-Pad28)") (class "Default")
      (node (ref "OUTPUT_TO_BELA") (pin "28") (pinfunction "28_28") (pintype "passive"))
    )
    (net (code "152") (name "unconnected-(OUTPUT_TO_BELA-Pad29)") (class "Default")
      (node (ref "OUTPUT_TO_BELA") (pin "29") (pinfunction "29_29") (pintype "passive"))
    )
    (net (code "153") (name "unconnected-(OUTPUT_TO_BELA-Pad30)") (class "Default")
      (node (ref "OUTPUT_TO_BELA") (pin "30") (pinfunction "30_30") (pintype "passive"))
    )
    (net (code "154") (name "unconnected-(OUTPUT_TO_BELA-Pad31)") (class "Default")
      (node (ref "OUTPUT_TO_BELA") (pin "31") (pinfunction "31_31") (pintype "passive"))
    )
    (net (code "155") (name "unconnected-(OUTPUT_TO_BELA-Pad32)") (class "Default")
      (node (ref "OUTPUT_TO_BELA") (pin "32") (pinfunction "32_32") (pintype "passive"))
    )
    (net (code "156") (name "unconnected-(OUTPUT_TO_BELA-Pad33)") (class "Default")
      (node (ref "OUTPUT_TO_BELA") (pin "33") (pinfunction "33_33") (pintype "passive"))
    )
    (net (code "157") (name "unconnected-(OUTPUT_TO_BELA-Pad34)") (class "Default")
      (node (ref "OUTPUT_TO_BELA") (pin "34") (pinfunction "34_34") (pintype "passive"))
    )
    (net (code "158") (name "unconnected-(P8-Pad1)") (class "Default")
      (node (ref "P8") (pin "1") (pinfunction "1_1") (pintype "passive"))
    )
    (net (code "159") (name "unconnected-(P8-Pad2)") (class "Default")
      (node (ref "P8") (pin "2") (pinfunction "2_2") (pintype "passive"))
    )
    (net (code "160") (name "unconnected-(P8-Pad3)") (class "Default")
      (node (ref "P8") (pin "3") (pinfunction "3_3") (pintype "passive"))
    )
    (net (code "161") (name "unconnected-(P8-Pad4)") (class "Default")
      (node (ref "P8") (pin "4") (pinfunction "4_4") (pintype "passive"))
    )
    (net (code "162") (name "unconnected-(P8-Pad5)") (class "Default")
      (node (ref "P8") (pin "5") (pinfunction "5_5") (pintype "passive"))
    )
    (net (code "163") (name "unconnected-(P8-Pad6)") (class "Default")
      (node (ref "P8") (pin "6") (pinfunction "6_6") (pintype "passive"))
    )
    (net (code "164") (name "unconnected-(P8-Pad8)") (class "Default")
      (node (ref "P8") (pin "8") (pinfunction "8_8") (pintype "passive"))
    )
    (net (code "165") (name "unconnected-(P8-Pad10)") (class "Default")
      (node (ref "P8") (pin "10") (pinfunction "10_10") (pintype "passive"))
    )
    (net (code "166") (name "unconnected-(P8-Pad12)") (class "Default")
      (node (ref "P8") (pin "12") (pinfunction "12_12") (pintype "passive"))
    )
    (net (code "167") (name "unconnected-(P8-Pad13)") (class "Default")
      (node (ref "P8") (pin "13") (pinfunction "13_13") (pintype "passive"))
    )
    (net (code "168") (name "unconnected-(P8-Pad14)") (class "Default")
      (node (ref "P8") (pin "14") (pinfunction "14_14") (pintype "passive"))
    )
    (net (code "169") (name "unconnected-(P8-Pad16)") (class "Default")
      (node (ref "P8") (pin "16") (pinfunction "16_16") (pintype "passive"))
    )
    (net (code "170") (name "unconnected-(P8-Pad17)") (class "Default")
      (node (ref "P8") (pin "17") (pinfunction "17_17") (pintype "passive"))
    )
    (net (code "171") (name "unconnected-(P8-Pad18)") (class "Default")
      (node (ref "P8") (pin "18") (pinfunction "18_18") (pintype "passive"))
    )
    (net (code "172") (name "unconnected-(P8-Pad19)") (class "Default")
      (node (ref "P8") (pin "19") (pinfunction "19_19") (pintype "passive"))
    )
    (net (code "173") (name "unconnected-(P8-Pad20)") (class "Default")
      (node (ref "P8") (pin "20") (pinfunction "20_20") (pintype "passive"))
    )
    (net (code "174") (name "unconnected-(P8-Pad21)") (class "Default")
      (node (ref "P8") (pin "21") (pinfunction "21_21") (pintype "passive"))
    )
    (net (code "175") (name "unconnected-(P8-Pad22)") (class "Default")
      (node (ref "P8") (pin "22") (pinfunction "22_22") (pintype "passive"))
    )
    (net (code "176") (name "unconnected-(P8-Pad23)") (class "Default")
      (node (ref "P8") (pin "23") (pinfunction "23_23") (pintype "passive"))
    )
    (net (code "177") (name "unconnected-(P8-Pad24)") (class "Default")
      (node (ref "P8") (pin "24") (pinfunction "24_24") (pintype "passive"))
    )
    (net (code "178") (name "unconnected-(P8-Pad25)") (class "Default")
      (node (ref "P8") (pin "25") (pinfunction "25_25") (pintype "passive"))
    )
    (net (code "179") (name "unconnected-(P8-Pad26)") (class "Default")
      (node (ref "P8") (pin "26") (pinfunction "26_26") (pintype "passive"))
    )
    (net (code "180") (name "unconnected-(P8-Pad31)") (class "Default")
      (node (ref "P8") (pin "31") (pinfunction "31_31") (pintype "passive"))
    )
    (net (code "181") (name "unconnected-(P8-Pad32)") (class "Default")
      (node (ref "P8") (pin "32") (pinfunction "32_32") (pintype "passive"))
    )
    (net (code "182") (name "unconnected-(P8-Pad33)") (class "Default")
      (node (ref "P8") (pin "33") (pinfunction "33_33") (pintype "passive"))
    )
    (net (code "183") (name "unconnected-(P8-Pad34)") (class "Default")
      (node (ref "P8") (pin "34") (pinfunction "34_34") (pintype "passive"))
    )
    (net (code "184") (name "unconnected-(P8-Pad35)") (class "Default")
      (node (ref "P8") (pin "35") (pinfunction "35_35") (pintype "passive"))
    )
    (net (code "185") (name "unconnected-(P8-Pad36)") (class "Default")
      (node (ref "P8") (pin "36") (pinfunction "36_36") (pintype "passive"))
    )
    (net (code "186") (name "unconnected-(P8-Pad37)") (class "Default")
      (node (ref "P8") (pin "37") (pinfunction "37_37") (pintype "passive"))
    )
    (net (code "187") (name "unconnected-(P8-Pad38)") (class "Default")
      (node (ref "P8") (pin "38") (pinfunction "38_38") (pintype "passive"))
    )
    (net (code "188") (name "unconnected-(P8-Pad39)") (class "Default")
      (node (ref "P8") (pin "39") (pinfunction "39_39") (pintype "passive"))
    )
    (net (code "189") (name "unconnected-(P8-Pad40)") (class "Default")
      (node (ref "P8") (pin "40") (pinfunction "40_40") (pintype "passive"))
    )
    (net (code "190") (name "unconnected-(P8-Pad41)") (class "Default")
      (node (ref "P8") (pin "41") (pinfunction "41_41") (pintype "passive"))
    )
    (net (code "191") (name "unconnected-(P8-Pad42)") (class "Default")
      (node (ref "P8") (pin "42") (pinfunction "42_42") (pintype "passive"))
    )
    (net (code "192") (name "unconnected-(P8-Pad43)") (class "Default")
      (node (ref "P8") (pin "43") (pinfunction "43_43") (pintype "passive"))
    )
    (net (code "193") (name "unconnected-(P8-Pad44)") (class "Default")
      (node (ref "P8") (pin "44") (pinfunction "44_44") (pintype "passive"))
    )
    (net (code "194") (name "unconnected-(P9-Pad2)") (class "Default")
      (node (ref "P9") (pin "2") (pinfunction "2_2") (pintype "passive"))
    )
    (net (code "195") (name "unconnected-(P9-Pad4)") (class "Default")
      (node (ref "P9") (pin "4") (pinfunction "4_4") (pintype "passive"))
    )
    (net (code "196") (name "unconnected-(P9-Pad5)") (class "Default")
      (node (ref "P9") (pin "5") (pinfunction "5_5") (pintype "passive"))
    )
    (net (code "197") (name "unconnected-(P9-Pad6)") (class "Default")
      (node (ref "P9") (pin "6") (pinfunction "6_6") (pintype "passive"))
    )
    (net (code "198") (name "unconnected-(P9-Pad7)") (class "Default")
      (node (ref "P9") (pin "7") (pinfunction "7_7") (pintype "passive"))
    )
    (net (code "199") (name "unconnected-(P9-Pad8)") (class "Default")
      (node (ref "P9") (pin "8") (pinfunction "8_8") (pintype "passive"))
    )
    (net (code "200") (name "unconnected-(P9-Pad9)") (class "Default")
      (node (ref "P9") (pin "9") (pinfunction "9_9") (pintype "passive"))
    )
    (net (code "201") (name "unconnected-(P9-Pad10)") (class "Default")
      (node (ref "P9") (pin "10") (pinfunction "10_10") (pintype "passive"))
    )
    (net (code "202") (name "unconnected-(P9-Pad12)") (class "Default")
      (node (ref "P9") (pin "12") (pinfunction "12_12") (pintype "passive"))
    )
    (net (code "203") (name "unconnected-(P9-Pad14)") (class "Default")
      (node (ref "P9") (pin "14") (pinfunction "14_14") (pintype "passive"))
    )
    (net (code "204") (name "unconnected-(P9-Pad16)") (class "Default")
      (node (ref "P9") (pin "16") (pinfunction "16_16") (pintype "passive"))
    )
    (net (code "205") (name "unconnected-(P9-Pad17)") (class "Default")
      (node (ref "P9") (pin "17") (pinfunction "17_17") (pintype "passive"))
    )
    (net (code "206") (name "unconnected-(P9-Pad18)") (class "Default")
      (node (ref "P9") (pin "18") (pinfunction "18_18") (pintype "passive"))
    )
    (net (code "207") (name "unconnected-(P9-Pad19)") (class "Default")
      (node (ref "P9") (pin "19") (pinfunction "19_19") (pintype "passive"))
    )
    (net (code "208") (name "unconnected-(P9-Pad20)") (class "Default")
      (node (ref "P9") (pin "20") (pinfunction "20_20") (pintype "passive"))
    )
    (net (code "209") (name "unconnected-(P9-Pad21)") (class "Default")
      (node (ref "P9") (pin "21") (pinfunction "21_21") (pintype "passive"))
    )
    (net (code "210") (name "unconnected-(P9-Pad22)") (class "Default")
      (node (ref "P9") (pin "22") (pinfunction "22_22") (pintype "passive"))
    )
    (net (code "211") (name "unconnected-(P9-Pad23)") (class "Default")
      (node (ref "P9") (pin "23") (pinfunction "23_23") (pintype "passive"))
    )
    (net (code "212") (name "unconnected-(P9-Pad24)") (class "Default")
      (node (ref "P9") (pin "24") (pinfunction "24_24") (pintype "passive"))
    )
    (net (code "213") (name "unconnected-(P9-Pad25)") (class "Default")
      (node (ref "P9") (pin "25") (pinfunction "25_25") (pintype "passive"))
    )
    (net (code "214") (name "unconnected-(P9-Pad26)") (class "Default")
      (node (ref "P9") (pin "26") (pinfunction "26_26") (pintype "passive"))
    )
    (net (code "215") (name "unconnected-(P9-Pad27)") (class "Default")
      (node (ref "P9") (pin "27") (pinfunction "27_27") (pintype "passive"))
    )
    (net (code "216") (name "unconnected-(P9-Pad28)") (class "Default")
      (node (ref "P9") (pin "28") (pinfunction "28_28") (pintype "passive"))
    )
    (net (code "217") (name "unconnected-(P9-Pad29)") (class "Default")
      (node (ref "P9") (pin "29") (pinfunction "29_29") (pintype "passive"))
    )
    (net (code "218") (name "unconnected-(P9-Pad30)") (class "Default")
      (node (ref "P9") (pin "30") (pinfunction "30_30") (pintype "passive"))
    )
    (net (code "219") (name "unconnected-(P9-Pad31)") (class "Default")
      (node (ref "P9") (pin "31") (pinfunction "31_31") (pintype "passive"))
    )
    (net (code "220") (name "unconnected-(P9-Pad32)") (class "Default")
      (node (ref "P9") (pin "32") (pinfunction "32_32") (pintype "passive"))
    )
    (net (code "221") (name "unconnected-(P9-Pad33)") (class "Default")
      (node (ref "P9") (pin "33") (pinfunction "33_33") (pintype "passive"))
    )
    (net (code "222") (name "unconnected-(P9-Pad34)") (class "Default")
      (node (ref "P9") (pin "34") (pinfunction "34_34") (pintype "passive"))
    )
    (net (code "223") (name "unconnected-(P9-Pad35)") (class "Default")
      (node (ref "P9") (pin "35") (pinfunction "35_35") (pintype "passive"))
    )
    (net (code "224") (name "unconnected-(P9-Pad36)") (class "Default")
      (node (ref "P9") (pin "36") (pinfunction "36_36") (pintype "passive"))
    )
    (net (code "225") (name "unconnected-(P9-Pad37)") (class "Default")
      (node (ref "P9") (pin "37") (pinfunction "37_37") (pintype "passive"))
    )
    (net (code "226") (name "unconnected-(P9-Pad38)") (class "Default")
      (node (ref "P9") (pin "38") (pinfunction "38_38") (pintype "passive"))
    )
    (net (code "227") (name "unconnected-(P9-Pad39)") (class "Default")
      (node (ref "P9") (pin "39") (pinfunction "39_39") (pintype "passive"))
    )
    (net (code "228") (name "unconnected-(P9-Pad40)") (class "Default")
      (node (ref "P9") (pin "40") (pinfunction "40_40") (pintype "passive"))
    )
    (net (code "229") (name "unconnected-(P9-Pad41)") (class "Default")
      (node (ref "P9") (pin "41") (pinfunction "41_41") (pintype "passive"))
    )
    (net (code "230") (name "unconnected-(P9-Pad42)") (class "Default")
      (node (ref "P9") (pin "42") (pinfunction "42_42") (pintype "passive"))
    )
    (net (code "231") (name "unconnected-(P9-Pad43)") (class "Default")
      (node (ref "P9") (pin "43") (pinfunction "43_43") (pintype "passive"))
    )
    (net (code "232") (name "unconnected-(P9-Pad44)") (class "Default")
      (node (ref "P9") (pin "44") (pinfunction "44_44") (pintype "passive"))
    )
    (net (code "233") (name "unconnected-(RACK_CON-Pad2)") (class "Default")
      (node (ref "RACK_CON") (pin "2") (pinfunction "2_2") (pintype "passive"))
    )
    (net (code "234") (name "unconnected-(RACK_CON-Pad3)") (class "Default")
      (node (ref "RACK_CON") (pin "3") (pinfunction "3_3") (pintype "passive"))
    )
    (net (code "235") (name "unconnected-(RACK_CON-Pad4)") (class "Default")
      (node (ref "RACK_CON") (pin "4") (pinfunction "4_4") (pintype "passive"))
    )
    (net (code "236") (name "unconnected-(RACK_CON-Pad6)") (class "Default")
      (node (ref "RACK_CON") (pin "6") (pinfunction "6_6") (pintype "passive"))
    )
    (net (code "237") (name "unconnected-(RACK_CON-Pad7)") (class "Default")
      (node (ref "RACK_CON") (pin "7") (pinfunction "7_7") (pintype "passive"))
    )
    (net (code "238") (name "unconnected-(RACK_CON-Pad8)") (class "Default")
      (node (ref "RACK_CON") (pin "8") (pinfunction "8_8") (pintype "passive"))
    )
    (net (code "239") (name "unconnected-(RACK_CON-Pad10)") (class "Default")
      (node (ref "RACK_CON") (pin "10") (pinfunction "10_10") (pintype "passive"))
    )
    (net (code "240") (name "unconnected-(RACK_CON-Pad12)") (class "Default")
      (node (ref "RACK_CON") (pin "12") (pinfunction "12_12") (pintype "passive"))
    )
    (net (code "241") (name "unconnected-(RACK_CON-Pad13)") (class "Default")
      (node (ref "RACK_CON") (pin "13") (pinfunction "13_13") (pintype "passive"))
    )
    (net (code "242") (name "unconnected-(RACK_CON-Pad14)") (class "Default")
      (node (ref "RACK_CON") (pin "14") (pinfunction "14_14") (pintype "passive"))
    )
    (net (code "243") (name "unconnected-(RACK_CON-Pad15)") (class "Default")
      (node (ref "RACK_CON") (pin "15") (pinfunction "15_15") (pintype "passive"))
    )
    (net (code "244") (name "unconnected-(RACK_CON-Pad16)") (class "Default")
      (node (ref "RACK_CON") (pin "16") (pinfunction "16_16") (pintype "passive"))
    )
  )
)
